# Linkable_LED_Matrix.net
KiCad netlist of a schematic drawn in EAGLE
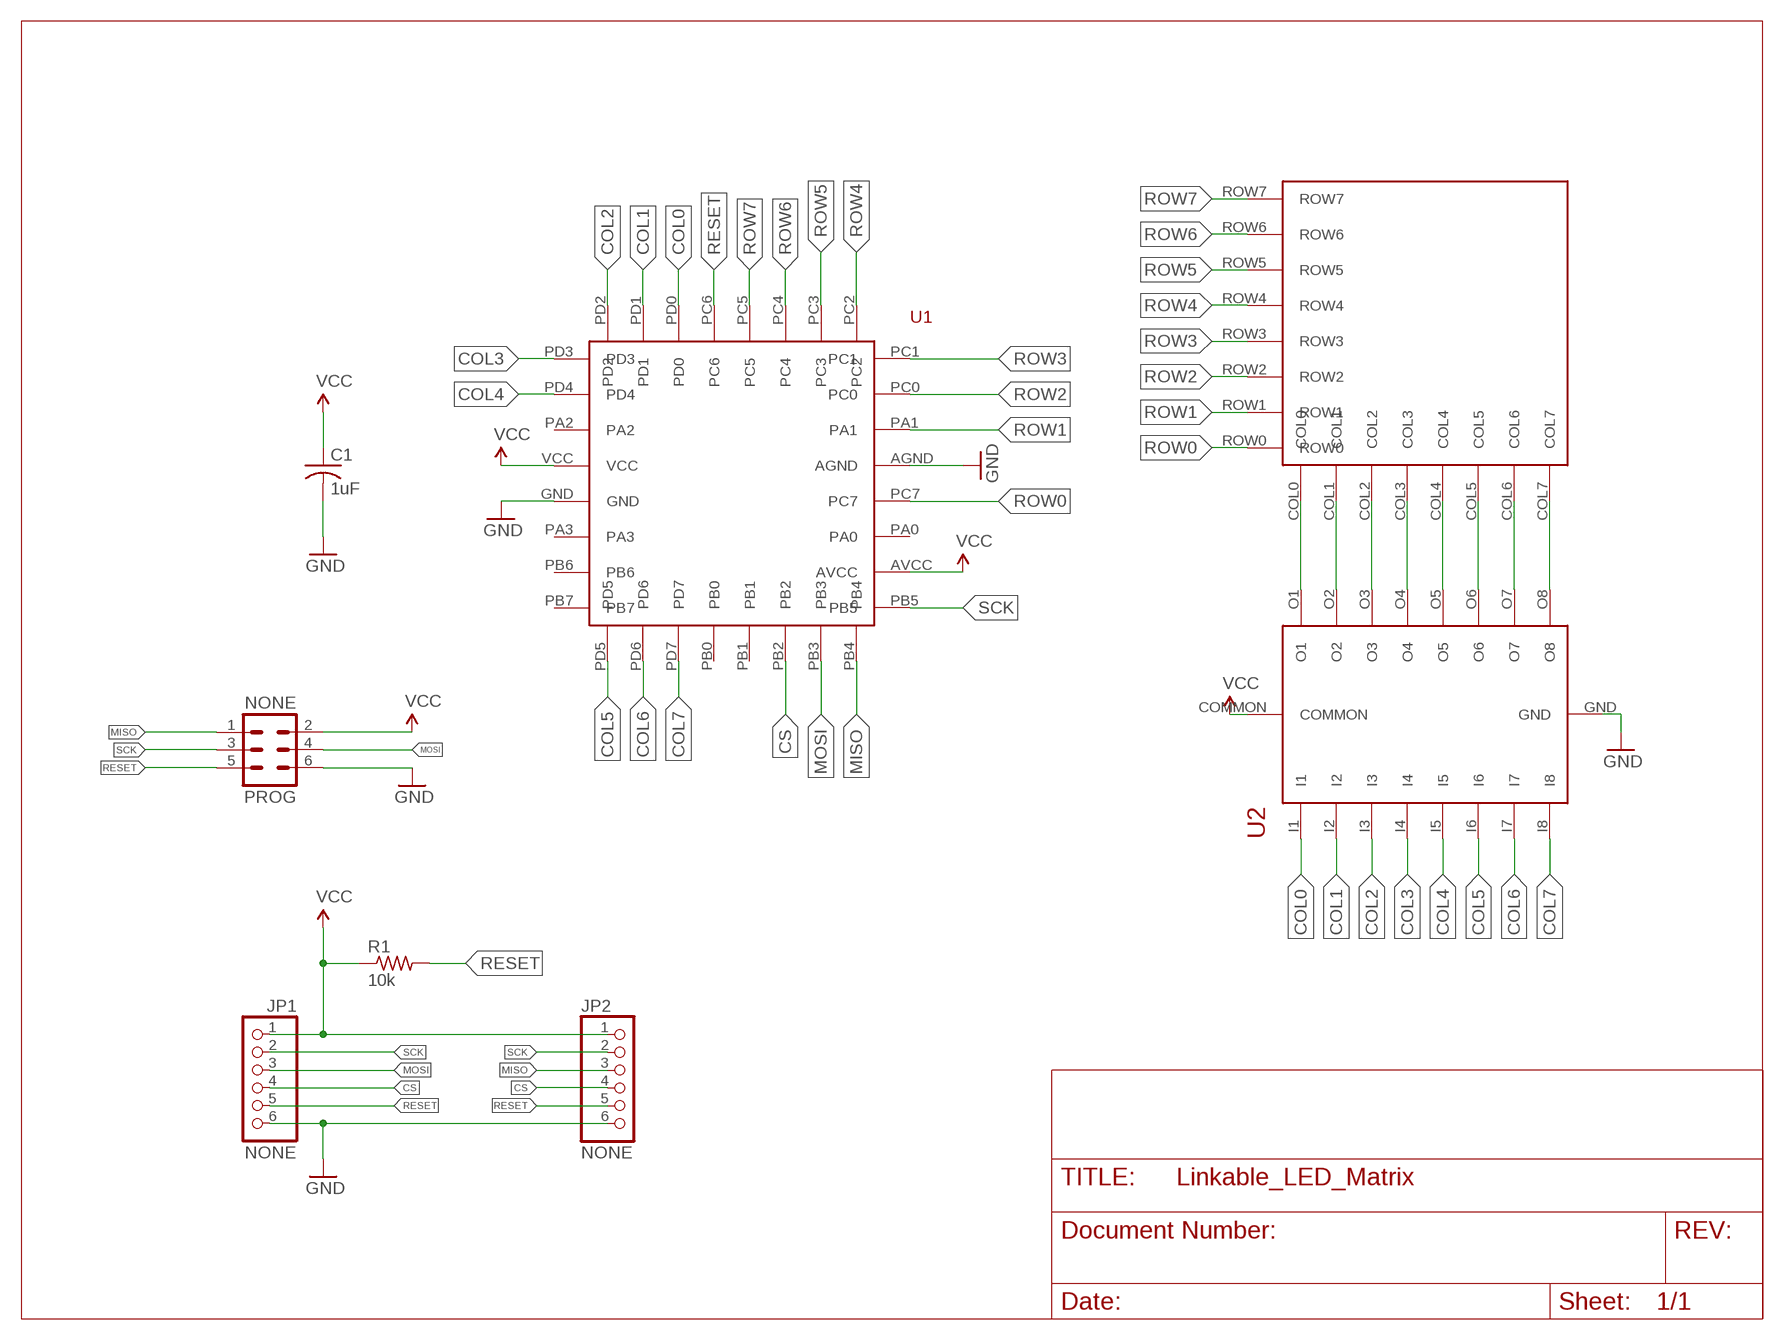
[diagram p0: schematic, sheet 1]

(export (version "E")
  (design (tool "Eeschema 10.0.6"))
  (components
    (comp (ref "C1")
      (value "1uF")
      (footprint "eagle-import:C0603")
      (libsource (lib "eagle-import") (part "C-USC0603"))
    )
    (comp (ref "JP1")
      (value "NONE")
      (footprint "eagle-import:1X06")
      (libsource (lib "eagle-import") (part "PINHD-1X6"))
    )
    (comp (ref "JP2")
      (value "NONE")
      (footprint "eagle-import:1X06")
      (libsource (lib "eagle-import") (part "PINHD-1X6"))
    )
    (comp (ref "LEDMATRIX")
      (value "8X8_LED_MATRIX")
      (footprint "eagle-import:8X8_LED_MATRIX")
      (libsource (lib "eagle-import") (part "8X8_LED_MATRIX"))
    )
    (comp (ref "PROG")
      (value "NONE")
      (footprint "eagle-import:MA03-2")
      (libsource (lib "eagle-import") (part "MA03-2"))
    )
    (comp (ref "R1")
      (value "10k")
      (footprint "eagle-import:R0603")
      (libsource (lib "eagle-import") (part "R-US_R0603"))
    )
    (comp (ref "U1")
      (value "ATTINY48")
      (footprint "eagle-import:ATTINY48")
      (libsource (lib "eagle-import") (part "ATTINY48"))
    )
    (comp (ref "U2")
      (value "ULN2803AFWG")
      (footprint "eagle-import:ULN2803AFWG")
      (libsource (lib "eagle-import") (part "ULN2803AFWG"))
    )
  )
  (nets
    (net (code "1") (name "COL0") (class "Default")
      (node (ref "U1") (pin "PD0") (pinfunction "PD0_PD0") (pintype "bidirectional"))
      (node (ref "U2") (pin "I1") (pinfunction "I1_I1") (pintype "bidirectional"))
    )
    (net (code "2") (name "COL1") (class "Default")
      (node (ref "U1") (pin "PD1") (pinfunction "PD1_PD1") (pintype "bidirectional"))
      (node (ref "U2") (pin "I2") (pinfunction "I2_I2") (pintype "bidirectional"))
    )
    (net (code "3") (name "COL2") (class "Default")
      (node (ref "U1") (pin "PD2") (pinfunction "PD2_PD2") (pintype "bidirectional"))
      (node (ref "U2") (pin "I3") (pinfunction "I3_I3") (pintype "bidirectional"))
    )
    (net (code "4") (name "COL3") (class "Default")
      (node (ref "U1") (pin "PD3") (pinfunction "PD3_PD3") (pintype "bidirectional"))
      (node (ref "U2") (pin "I4") (pinfunction "I4_I4") (pintype "bidirectional"))
    )
    (net (code "5") (name "COL4") (class "Default")
      (node (ref "U1") (pin "PD4") (pinfunction "PD4_PD4") (pintype "bidirectional"))
      (node (ref "U2") (pin "I5") (pinfunction "I5_I5") (pintype "bidirectional"))
    )
    (net (code "6") (name "COL5") (class "Default")
      (node (ref "U1") (pin "PD5") (pinfunction "PD5_PD5") (pintype "bidirectional"))
      (node (ref "U2") (pin "I6") (pinfunction "I6_I6") (pintype "bidirectional"))
    )
    (net (code "7") (name "COL6") (class "Default")
      (node (ref "U1") (pin "PD6") (pinfunction "PD6_PD6") (pintype "bidirectional"))
      (node (ref "U2") (pin "I7") (pinfunction "I7_I7") (pintype "bidirectional"))
    )
    (net (code "8") (name "COL7") (class "Default")
      (node (ref "U1") (pin "PD7") (pinfunction "PD7_PD7") (pintype "bidirectional"))
      (node (ref "U2") (pin "I8") (pinfunction "I8_I8") (pintype "bidirectional"))
    )
    (net (code "9") (name "CS") (class "Default")
      (node (ref "JP1") (pin "4") (pinfunction "4_4") (pintype "passive"))
      (node (ref "JP2") (pin "4") (pinfunction "4_4") (pintype "passive"))
      (node (ref "U1") (pin "PB2") (pinfunction "PB2_PB2") (pintype "bidirectional"))
    )
    (net (code "10") (name "GND") (class "Default")
      (node (ref "C1") (pin "2") (pinfunction "2_2") (pintype "passive"))
      (node (ref "JP1") (pin "6") (pinfunction "6_6") (pintype "passive"))
      (node (ref "JP2") (pin "6") (pinfunction "6_6") (pintype "passive"))
      (node (ref "PROG") (pin "6") (pinfunction "6_6") (pintype "passive"))
      (node (ref "U1") (pin "AGND") (pinfunction "AGND_AGND") (pintype "bidirectional"))
      (node (ref "U1") (pin "GND") (pinfunction "GND_GND") (pintype "bidirectional"))
      (node (ref "U2") (pin "GND") (pinfunction "GND_GND") (pintype "bidirectional"))
    )
    (net (code "11") (name "MISO") (class "Default")
      (node (ref "JP2") (pin "3") (pinfunction "3_3") (pintype "passive"))
      (node (ref "PROG") (pin "1") (pinfunction "1_1") (pintype "passive"))
      (node (ref "U1") (pin "PB4") (pinfunction "PB4_PB4") (pintype "bidirectional"))
    )
    (net (code "12") (name "MOSI") (class "Default")
      (node (ref "JP1") (pin "3") (pinfunction "3_3") (pintype "passive"))
      (node (ref "PROG") (pin "4") (pinfunction "4_4") (pintype "passive"))
      (node (ref "U1") (pin "PB3") (pinfunction "PB3_PB3") (pintype "bidirectional"))
    )
    (net (code "13") (name "Net-(LEDMATRIX-PadCOL0)") (class "Default")
      (node (ref "LEDMATRIX") (pin "COL0") (pinfunction "COL0_COL0") (pintype "bidirectional"))
      (node (ref "U2") (pin "O1") (pinfunction "O1_O1") (pintype "bidirectional"))
    )
    (net (code "14") (name "Net-(LEDMATRIX-PadCOL1)") (class "Default")
      (node (ref "LEDMATRIX") (pin "COL1") (pinfunction "COL1_COL1") (pintype "bidirectional"))
      (node (ref "U2") (pin "O2") (pinfunction "O2_O2") (pintype "bidirectional"))
    )
    (net (code "15") (name "Net-(LEDMATRIX-PadCOL2)") (class "Default")
      (node (ref "LEDMATRIX") (pin "COL2") (pinfunction "COL2_COL2") (pintype "bidirectional"))
      (node (ref "U2") (pin "O3") (pinfunction "O3_O3") (pintype "bidirectional"))
    )
    (net (code "16") (name "Net-(LEDMATRIX-PadCOL3)") (class "Default")
      (node (ref "LEDMATRIX") (pin "COL3") (pinfunction "COL3_COL3") (pintype "bidirectional"))
      (node (ref "U2") (pin "O4") (pinfunction "O4_O4") (pintype "bidirectional"))
    )
    (net (code "17") (name "Net-(LEDMATRIX-PadCOL4)") (class "Default")
      (node (ref "LEDMATRIX") (pin "COL4") (pinfunction "COL4_COL4") (pintype "bidirectional"))
      (node (ref "U2") (pin "O5") (pinfunction "O5_O5") (pintype "bidirectional"))
    )
    (net (code "18") (name "Net-(LEDMATRIX-PadCOL5)") (class "Default")
      (node (ref "LEDMATRIX") (pin "COL5") (pinfunction "COL5_COL5") (pintype "bidirectional"))
      (node (ref "U2") (pin "O6") (pinfunction "O6_O6") (pintype "bidirectional"))
    )
    (net (code "19") (name "Net-(LEDMATRIX-PadCOL6)") (class "Default")
      (node (ref "LEDMATRIX") (pin "COL6") (pinfunction "COL6_COL6") (pintype "bidirectional"))
      (node (ref "U2") (pin "O7") (pinfunction "O7_O7") (pintype "bidirectional"))
    )
    (net (code "20") (name "Net-(LEDMATRIX-PadCOL7)") (class "Default")
      (node (ref "LEDMATRIX") (pin "COL7") (pinfunction "COL7_COL7") (pintype "bidirectional"))
      (node (ref "U2") (pin "O8") (pinfunction "O8_O8") (pintype "bidirectional"))
    )
    (net (code "21") (name "RESET") (class "Default")
      (node (ref "JP1") (pin "5") (pinfunction "5_5") (pintype "passive"))
      (node (ref "JP2") (pin "5") (pinfunction "5_5") (pintype "passive"))
      (node (ref "PROG") (pin "5") (pinfunction "5_5") (pintype "passive"))
      (node (ref "R1") (pin "2") (pinfunction "2_2") (pintype "passive"))
      (node (ref "U1") (pin "PC6") (pinfunction "PC6_PC6") (pintype "bidirectional"))
    )
    (net (code "22") (name "ROW0") (class "Default")
      (node (ref "LEDMATRIX") (pin "ROW0") (pinfunction "ROW0_ROW0") (pintype "bidirectional"))
      (node (ref "U1") (pin "PC7") (pinfunction "PC7_PC7") (pintype "bidirectional"))
    )
    (net (code "23") (name "ROW1") (class "Default")
      (node (ref "LEDMATRIX") (pin "ROW1") (pinfunction "ROW1_ROW1") (pintype "bidirectional"))
      (node (ref "U1") (pin "PA1") (pinfunction "PA1_PA1") (pintype "bidirectional"))
    )
    (net (code "24") (name "ROW2") (class "Default")
      (node (ref "LEDMATRIX") (pin "ROW2") (pinfunction "ROW2_ROW2") (pintype "bidirectional"))
      (node (ref "U1") (pin "PC0") (pinfunction "PC0_PC0") (pintype "bidirectional"))
    )
    (net (code "25") (name "ROW3") (class "Default")
      (node (ref "LEDMATRIX") (pin "ROW3") (pinfunction "ROW3_ROW3") (pintype "bidirectional"))
      (node (ref "U1") (pin "PC1") (pinfunction "PC1_PC1") (pintype "bidirectional"))
    )
    (net (code "26") (name "ROW4") (class "Default")
      (node (ref "LEDMATRIX") (pin "ROW4") (pinfunction "ROW4_ROW4") (pintype "bidirectional"))
      (node (ref "U1") (pin "PC2") (pinfunction "PC2_PC2") (pintype "bidirectional"))
    )
    (net (code "27") (name "ROW5") (class "Default")
      (node (ref "LEDMATRIX") (pin "ROW5") (pinfunction "ROW5_ROW5") (pintype "bidirectional"))
      (node (ref "U1") (pin "PC3") (pinfunction "PC3_PC3") (pintype "bidirectional"))
    )
    (net (code "28") (name "ROW6") (class "Default")
      (node (ref "LEDMATRIX") (pin "ROW6") (pinfunction "ROW6_ROW6") (pintype "bidirectional"))
      (node (ref "U1") (pin "PC4") (pinfunction "PC4_PC4") (pintype "bidirectional"))
    )
    (net (code "29") (name "ROW7") (class "Default")
      (node (ref "LEDMATRIX") (pin "ROW7") (pinfunction "ROW7_ROW7") (pintype "bidirectional"))
      (node (ref "U1") (pin "PC5") (pinfunction "PC5_PC5") (pintype "bidirectional"))
    )
    (net (code "30") (name "SCK") (class "Default")
      (node (ref "JP1") (pin "2") (pinfunction "2_2") (pintype "passive"))
      (node (ref "JP2") (pin "2") (pinfunction "2_2") (pintype "passive"))
      (node (ref "PROG") (pin "3") (pinfunction "3_3") (pintype "passive"))
      (node (ref "U1") (pin "PB5") (pinfunction "PB5_PB5") (pintype "bidirectional"))
    )
    (net (code "31") (name "VCC") (class "Default")
      (node (ref "C1") (pin "1") (pinfunction "1_1") (pintype "passive"))
      (node (ref "JP1") (pin "1") (pinfunction "1_1") (pintype "passive"))
      (node (ref "JP2") (pin "1") (pinfunction "1_1") (pintype "passive"))
      (node (ref "PROG") (pin "2") (pinfunction "2_2") (pintype "passive"))
      (node (ref "R1") (pin "1") (pinfunction "1_1") (pintype "passive"))
      (node (ref "U1") (pin "AVCC") (pinfunction "AVCC_AVCC") (pintype "bidirectional"))
      (node (ref "U1") (pin "VCC") (pinfunction "VCC_VCC") (pintype "bidirectional"))
      (node (ref "U2") (pin "COMMON") (pinfunction "COMMON_COMMON") (pintype "bidirectional"))
    )
    (net (code "32") (name "unconnected-(U1-PadPA0)") (class "Default")
      (node (ref "U1") (pin "PA0") (pinfunction "PA0_PA0") (pintype "bidirectional"))
    )
    (net (code "33") (name "unconnected-(U1-PadPA2)") (class "Default")
      (node (ref "U1") (pin "PA2") (pinfunction "PA2_PA2") (pintype "bidirectional"))
    )
    (net (code "34") (name "unconnected-(U1-PadPA3)") (class "Default")
      (node (ref "U1") (pin "PA3") (pinfunction "PA3_PA3") (pintype "bidirectional"))
    )
    (net (code "35") (name "unconnected-(U1-PadPB0)") (class "Default")
      (node (ref "U1") (pin "PB0") (pinfunction "PB0_PB0") (pintype "bidirectional"))
    )
    (net (code "36") (name "unconnected-(U1-PadPB1)") (class "Default")
      (node (ref "U1") (pin "PB1") (pinfunction "PB1_PB1") (pintype "bidirectional"))
    )
    (net (code "37") (name "unconnected-(U1-PadPB6)") (class "Default")
      (node (ref "U1") (pin "PB6") (pinfunction "PB6_PB6") (pintype "bidirectional"))
    )
    (net (code "38") (name "unconnected-(U1-PadPB7)") (class "Default")
      (node (ref "U1") (pin "PB7") (pinfunction "PB7_PB7") (pintype "bidirectional"))
    )
  )
)
